# SCH_NFC-Business-Card.net
KiCad netlist of a schematic drawn in EasyEDA
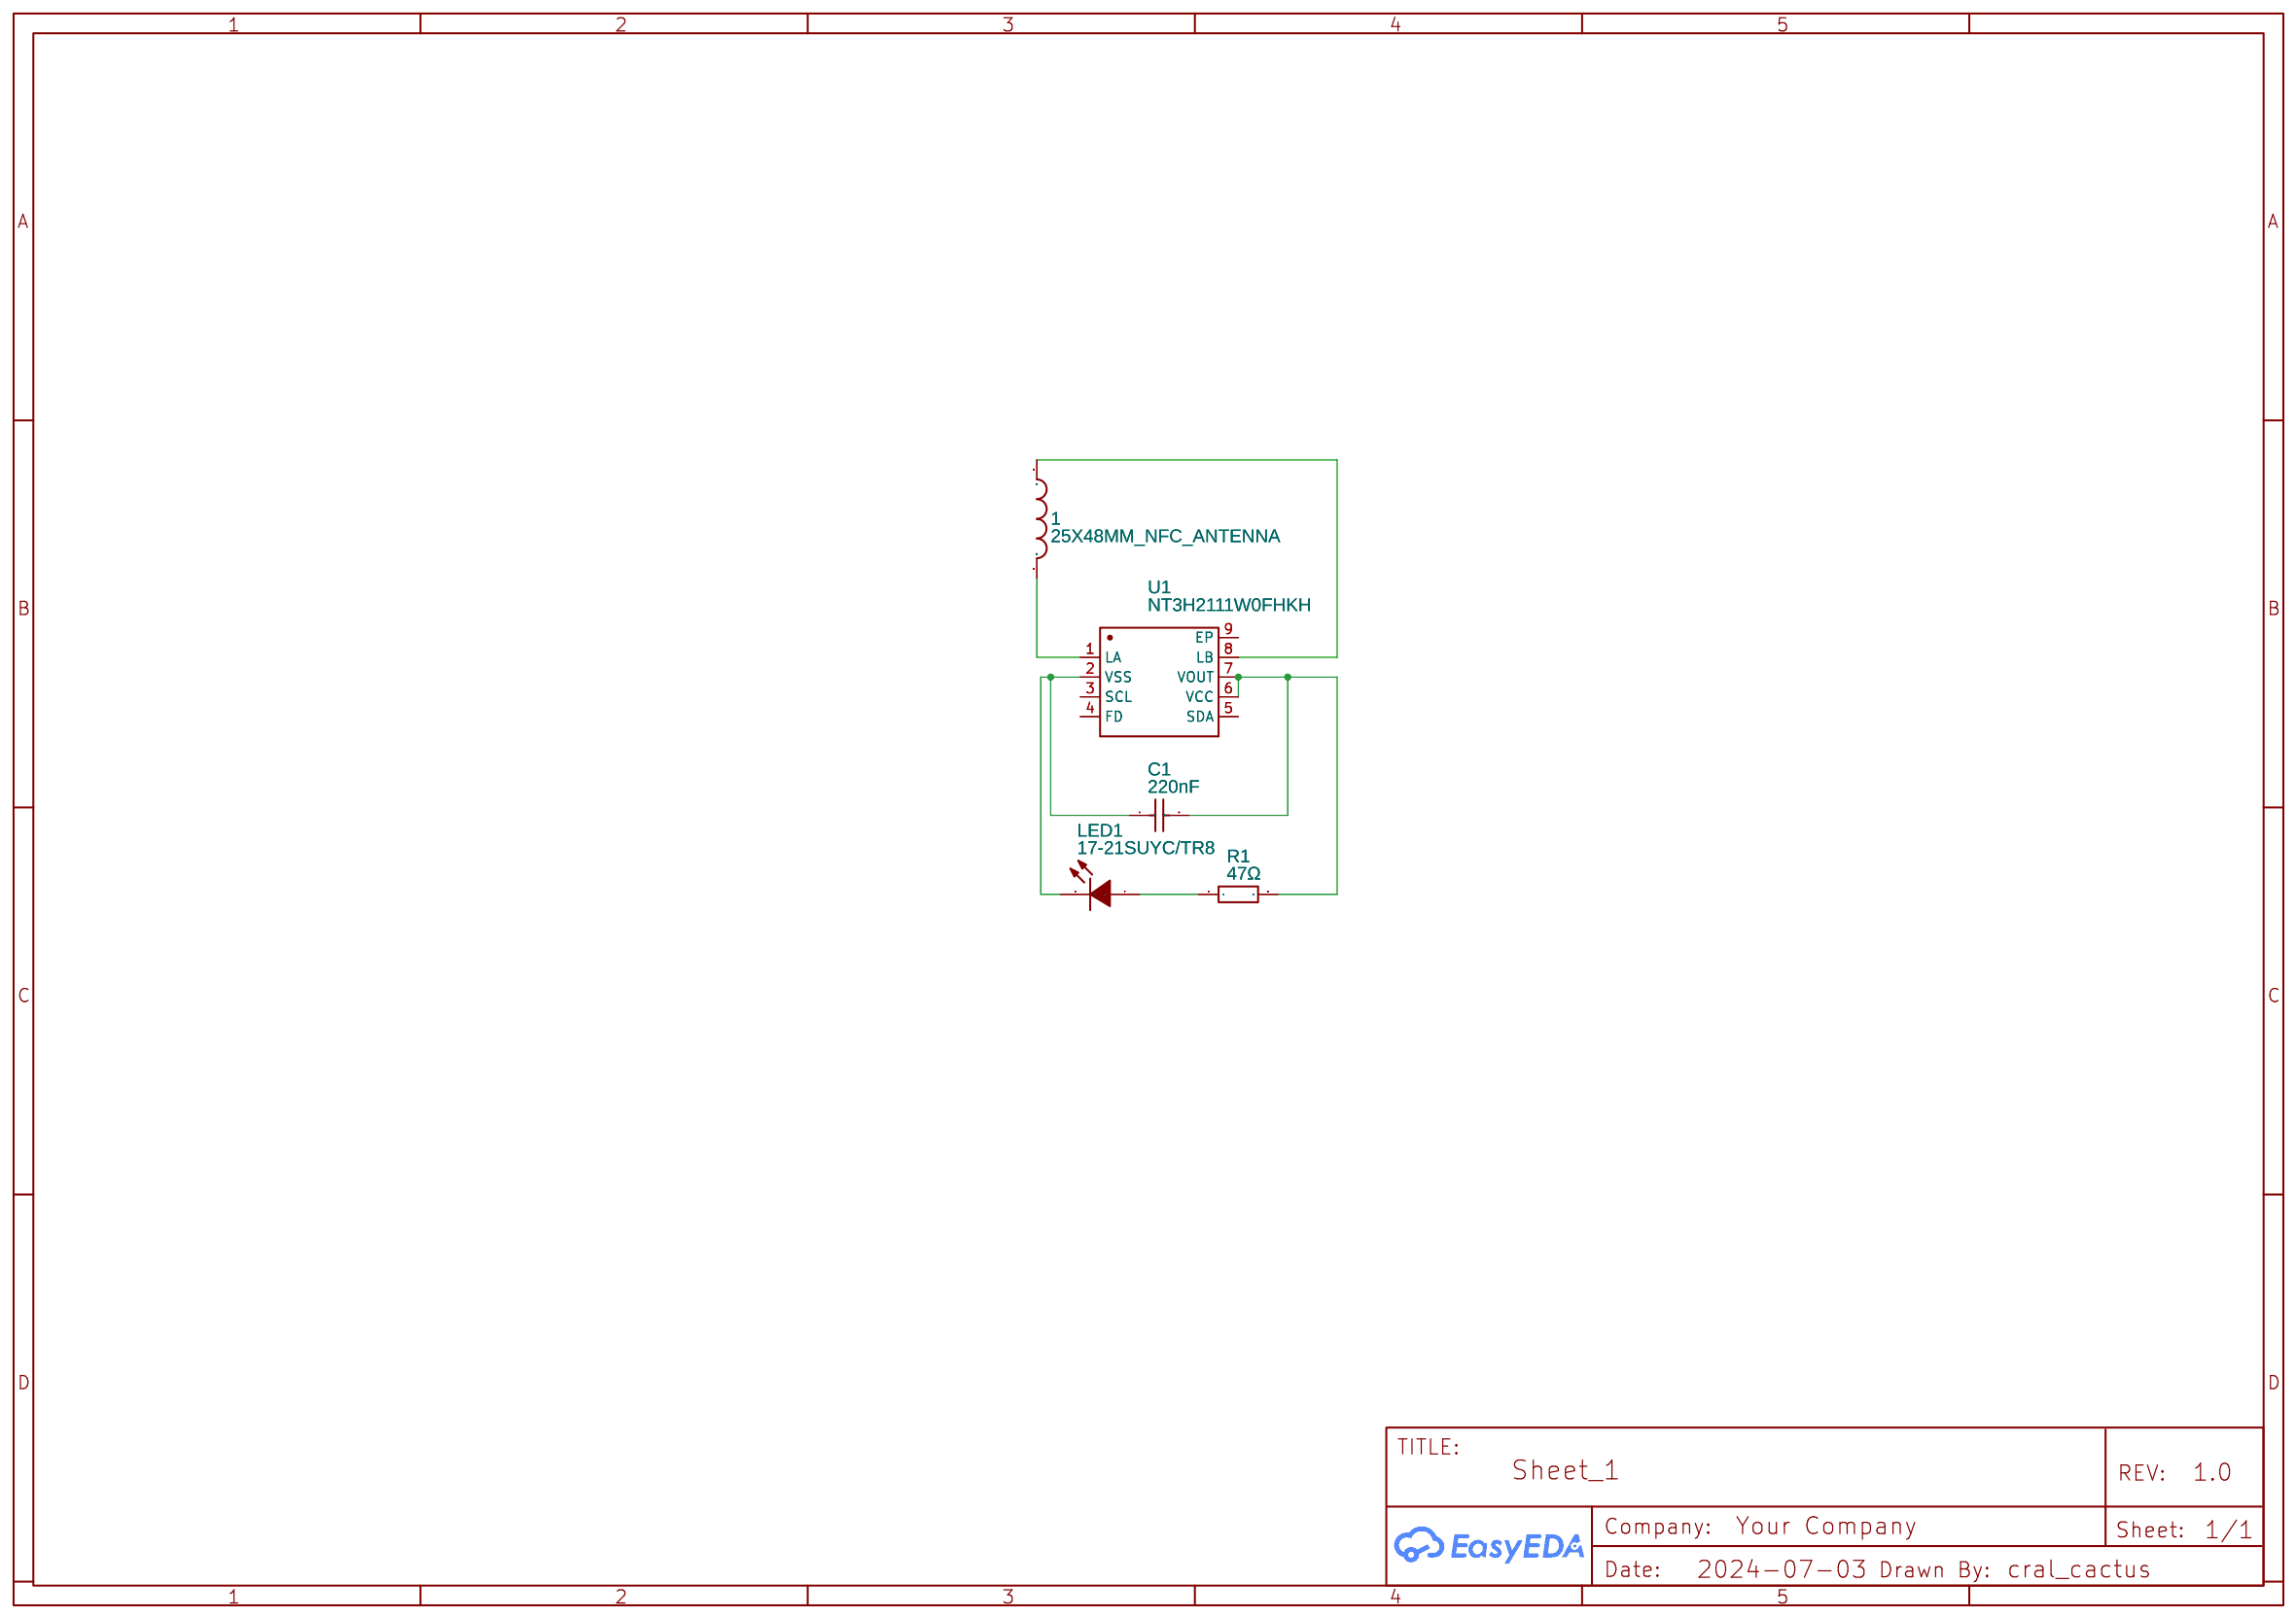
[diagram p0: schematic sheet]

(export (version "E")
  (design (tool "Eeschema 10.0.6"))
  (components
    (comp (ref "1") (value "25X48MM_NFC_ANTENNA") (libsource (lib "") (part "25X48MM_NFC_ANTENNA")))
    (comp (ref "C1")
      (value "220nF")
      (fields
        (field (name "Manufacturer Part") "CL10B224KA8NNNC")
        (field (name "Manufacturer") "SAMSUNG(三星)")
      )
      (libsource (lib "") (part "CL10B224KA8NNNC"))
    )
    (comp (ref "LED1")
      (value "17-21SUYC/TR8")
      (fields (field (name "Manufacturer Part") "KT-0805黄灯") (field (name "Manufacturer") "KENTO"))
      (libsource (lib "") (part "17-21SUYC/TR8"))
    )
    (comp (ref "R1")
      (value "47Ω")
      (fields
        (field (name "Manufacturer Part") "0603WAF470JT5E")
        (field (name "Manufacturer") "UNI-ROYAL(厚声)")
      )
      (libsource (lib "") (part "0603WAF470JT5E"))
    )
    (comp (ref "U1")
      (value "NT3H2111W0FHKH")
      (fields (field (name "Manufacturer") "NXP(恩智浦)"))
      (libsource (lib "") (part "NT3H2111W0FHKH"))
    )
  )
  (nets
    (net (code "1") (name "Net-(LED1-+)") (class "Default")
      (node (ref "LED1") (pin "1") (pinfunction "+_1") (pintype "unspecified"))
      (node (ref "R1") (pin "1") (pinfunction "1_1") (pintype "input"))
    )
    (net (code "2") (name "Net-(LED1--)") (class "Default")
      (node (ref "C1") (pin "1") (pinfunction "1_1") (pintype "input"))
      (node (ref "LED1") (pin "2") (pinfunction "-_2") (pintype "unspecified"))
      (node (ref "U1") (pin "2") (pinfunction "VSS_2") (pintype "unspecified"))
    )
    (net (code "3") (name "Net-(U1-LA)") (class "Default")
      (node (ref "1") (pin "P$2") (pinfunction "P$2_P$2") (pintype "bidirectional"))
      (node (ref "U1") (pin "1") (pinfunction "LA_1") (pintype "unspecified"))
    )
    (net (code "4") (name "Net-(U1-LB)") (class "Default")
      (node (ref "1") (pin "P$1") (pinfunction "P$1_P$1") (pintype "bidirectional"))
      (node (ref "U1") (pin "8") (pinfunction "LB_8") (pintype "unspecified"))
    )
    (net (code "5") (name "Net-(U1-VCC)") (class "Default")
      (node (ref "C1") (pin "2") (pinfunction "2_2") (pintype "input"))
      (node (ref "R1") (pin "2") (pinfunction "2_2") (pintype "input"))
      (node (ref "U1") (pin "6") (pinfunction "VCC_6") (pintype "unspecified"))
      (node (ref "U1") (pin "7") (pinfunction "VOUT_7") (pintype "unspecified"))
    )
    (net (code "6") (name "unconnected-(U1-EP-Pad9)") (class "Default")
      (node (ref "U1") (pin "9") (pinfunction "EP_9") (pintype "unspecified"))
    )
    (net (code "7") (name "unconnected-(U1-FD-Pad4)") (class "Default")
      (node (ref "U1") (pin "4") (pinfunction "FD_4") (pintype "unspecified"))
    )
    (net (code "8") (name "unconnected-(U1-SCL-Pad3)") (class "Default")
      (node (ref "U1") (pin "3") (pinfunction "SCL_3") (pintype "unspecified"))
    )
    (net (code "9") (name "unconnected-(U1-SDA-Pad5)") (class "Default")
      (node (ref "U1") (pin "5") (pinfunction "SDA_5") (pintype "unspecified"))
    )
  )
)
